# button.net
KiCad netlist of a schematic drawn in Altium Designer
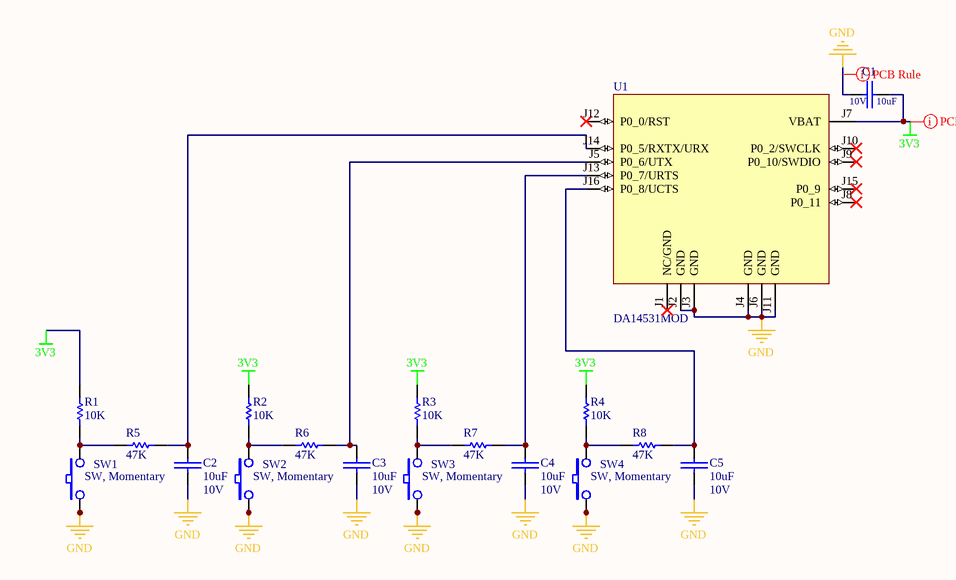
[diagram p0: button.SchDoc]

(export (version "E")
  (design (tool "Eeschema 10.0.6"))
  (components
    (comp (ref "C1")
      (value "10uF")
      (footprint "CAPC1608X10N")
      (description "Capacitor, 10uF, 10V, SM")
      (fields
        (field (name "MANUFACTURER'S PART #") "GRM188R61A106KE69D")
        (field (name "MANUFACTURER") "Murata")
        (field (name "VOLTAGE RATING") "10V")
      )
      (libsource (lib "Low Power Bluetooth PMOD RevA") (part "CI-10uF-10V-X5R-SR-MRT"))
    )
    (comp (ref "C2")
      (value "10uF")
      (footprint "CAPC1608X10N")
      (description "Capacitor, 10uF, 10V, SM")
      (fields
        (field (name "MANUFACTURER'S PART #") "GRM188R61A106KE69D")
        (field (name "MANUFACTURER") "Murata")
        (field (name "VOLTAGE RATING") "10V")
      )
      (libsource (lib "Low Power Bluetooth PMOD RevA") (part "CI-10uF-10V-X5R-SR-MRT"))
    )
    (comp (ref "C3")
      (value "10uF")
      (footprint "CAPC1608X10N")
      (description "Capacitor, 10uF, 10V, SM")
      (fields
        (field (name "MANUFACTURER'S PART #") "GRM188R61A106KE69D")
        (field (name "MANUFACTURER") "Murata")
        (field (name "VOLTAGE RATING") "10V")
      )
      (libsource (lib "Low Power Bluetooth PMOD RevA") (part "CI-10uF-10V-X5R-SR-MRT"))
    )
    (comp (ref "C4")
      (value "10uF")
      (footprint "CAPC1608X10N")
      (description "Capacitor, 10uF, 10V, SM")
      (fields
        (field (name "MANUFACTURER'S PART #") "GRM188R61A106KE69D")
        (field (name "MANUFACTURER") "Murata")
        (field (name "VOLTAGE RATING") "10V")
      )
      (libsource (lib "Low Power Bluetooth PMOD RevA") (part "CI-10uF-10V-X5R-SR-MRT"))
    )
    (comp (ref "C5")
      (value "10uF")
      (footprint "CAPC1608X10N")
      (description "Capacitor, 10uF, 10V, SM")
      (fields
        (field (name "MANUFACTURER'S PART #") "GRM188R61A106KE69D")
        (field (name "MANUFACTURER") "Murata")
        (field (name "VOLTAGE RATING") "10V")
      )
      (libsource (lib "Low Power Bluetooth PMOD RevA") (part "CI-10uF-10V-X5R-SR-MRT"))
    )
    (comp (ref "R1")
      (value "10K")
      (footprint "RESC1608X06N")
      (description "Resistor, 10K ohms, 1/8W, 1%, SM")
      (fields
        (field (name "MANUFACTURER'S PART #") "RK73H1JTTD1002F")
        (field (name "MANUFACTURER") "KOA Speer")
      )
      (libsource (lib "Low Power Bluetooth PMOD RevA") (part "RP-10K-SR-KOA"))
    )
    (comp (ref "R2")
      (value "10K")
      (footprint "RESC1608X06N")
      (description "Resistor, 10K ohms, 1/8W, 1%, SM")
      (fields
        (field (name "MANUFACTURER'S PART #") "RK73H1JTTD1002F")
        (field (name "MANUFACTURER") "KOA Speer")
      )
      (libsource (lib "Low Power Bluetooth PMOD RevA") (part "RP-10K-SR-KOA"))
    )
    (comp (ref "R3")
      (value "10K")
      (footprint "RESC1608X06N")
      (description "Resistor, 10K ohms, 1/8W, 1%, SM")
      (fields
        (field (name "MANUFACTURER'S PART #") "RK73H1JTTD1002F")
        (field (name "MANUFACTURER") "KOA Speer")
      )
      (libsource (lib "Low Power Bluetooth PMOD RevA") (part "RP-10K-SR-KOA"))
    )
    (comp (ref "R4")
      (value "10K")
      (footprint "RESC1608X06N")
      (description "Resistor, 10K ohms, 1/8W, 1%, SM")
      (fields
        (field (name "MANUFACTURER'S PART #") "RK73H1JTTD1002F")
        (field (name "MANUFACTURER") "KOA Speer")
      )
      (libsource (lib "Low Power Bluetooth PMOD RevA") (part "RP-10K-SR-KOA"))
    )
    (comp (ref "R5")
      (value "47K")
      (footprint "RESC1608X06N")
      (description "Resistor, 47K ohms, 1/8W, 1%, SM")
      (fields
        (field (name "MANUFACTURER'S PART #") "RK73H1JTTD6802F")
        (field (name "MANUFACTURER") "KOA Speer")
      )
      (libsource (lib "Low Power Bluetooth PMOD RevA") (part "RP-47K-SR-KOA"))
    )
    (comp (ref "R6")
      (value "47K")
      (footprint "RESC1608X06N")
      (description "Resistor, 47K ohms, 1/8W, 1%, SM")
      (fields
        (field (name "MANUFACTURER'S PART #") "RK73H1JTTD6802F")
        (field (name "MANUFACTURER") "KOA Speer")
      )
      (libsource (lib "Low Power Bluetooth PMOD RevA") (part "RP-47K-SR-KOA"))
    )
    (comp (ref "R7")
      (value "47K")
      (footprint "RESC1608X06N")
      (description "Resistor, 47K ohms, 1/8W, 1%, SM")
      (fields
        (field (name "MANUFACTURER'S PART #") "RK73H1JTTD6802F")
        (field (name "MANUFACTURER") "KOA Speer")
      )
      (libsource (lib "Low Power Bluetooth PMOD RevA") (part "RP-47K-SR-KOA"))
    )
    (comp (ref "R8")
      (value "47K")
      (footprint "RESC1608X06N")
      (description "Resistor, 47K ohms, 1/8W, 1%, SM")
      (fields
        (field (name "MANUFACTURER'S PART #") "RK73H1JTTD6802F")
        (field (name "MANUFACTURER") "KOA Speer")
      )
      (libsource (lib "Low Power Bluetooth PMOD RevA") (part "RP-47K-SR-KOA"))
    )
    (comp (ref "SW1")
      (value "SW, Momentary")
      (footprint "SW_PTS810")
      (description "Switch, Pushbutton, Top Actuated, SM")
      (fields
        (field (name "MANUFACTURER'S PART #") "PTS810 SJG 250 SMTR LFS")
        (field (name "MANUFACTURER") "C&K Components")
      )
      (libsource (lib "Low Power Bluetooth PMOD RevA") (part "SW-PTS810SJG250-SR-CKC"))
    )
    (comp (ref "SW2")
      (value "SW, Momentary")
      (footprint "SW_PTS810")
      (description "Switch, Pushbutton, Top Actuated, SM")
      (fields
        (field (name "MANUFACTURER'S PART #") "PTS810 SJG 250 SMTR LFS")
        (field (name "MANUFACTURER") "C&K Components")
      )
      (libsource (lib "Low Power Bluetooth PMOD RevA") (part "SW-PTS810SJG250-SR-CKC"))
    )
    (comp (ref "SW3")
      (value "SW, Momentary")
      (footprint "SW_PTS810")
      (description "Switch, Pushbutton, Top Actuated, SM")
      (fields
        (field (name "MANUFACTURER'S PART #") "PTS810 SJG 250 SMTR LFS")
        (field (name "MANUFACTURER") "C&K Components")
      )
      (libsource (lib "Low Power Bluetooth PMOD RevA") (part "SW-PTS810SJG250-SR-CKC"))
    )
    (comp (ref "SW4")
      (value "SW, Momentary")
      (footprint "SW_PTS810")
      (description "Switch, Pushbutton, Top Actuated, SM")
      (fields
        (field (name "MANUFACTURER'S PART #") "PTS810 SJG 250 SMTR LFS")
        (field (name "MANUFACTURER") "C&K Components")
      )
      (libsource (lib "Low Power Bluetooth PMOD RevA") (part "SW-PTS810SJG250-SR-CKC"))
    )
    (comp (ref "U1")
      (value "DA14531MOD")
      (footprint "DLG_DA14531MOD-00F01002")
      (description "DA14531MOD, Bluetooth Low Energy 5.1 Module, SM")
      (libsource (lib "Low Power Bluetooth PMOD RevA") (part "UD-DA14531MOD-00F01002-SR-DLG"))
    )
  )
  (nets
    (net (code "1") (name "3V3") (class "Default")
      (node (ref "C1") (pin "1") (pinfunction "1_1") (pintype "passive"))
      (node (ref "R1") (pin "1") (pinfunction "1_1") (pintype "passive"))
      (node (ref "R2") (pin "1") (pinfunction "1_1") (pintype "passive"))
      (node (ref "R3") (pin "1") (pinfunction "1_1") (pintype "passive"))
      (node (ref "R4") (pin "1") (pinfunction "1_1") (pintype "passive"))
      (node (ref "U1") (pin "J7") (pinfunction "VBAT_J7") (pintype "power_in"))
    )
    (net (code "2") (name "GND") (class "Default")
      (node (ref "C1") (pin "2") (pinfunction "2_2") (pintype "passive"))
      (node (ref "C2") (pin "2") (pinfunction "2_2") (pintype "passive"))
      (node (ref "C3") (pin "2") (pinfunction "2_2") (pintype "passive"))
      (node (ref "C4") (pin "2") (pinfunction "2_2") (pintype "passive"))
      (node (ref "C5") (pin "2") (pinfunction "2_2") (pintype "passive"))
      (node (ref "SW1") (pin "1") (pinfunction "1_1") (pintype "passive"))
      (node (ref "SW1") (pin "2") (pinfunction "2_2") (pintype "passive"))
      (node (ref "SW2") (pin "1") (pinfunction "1_1") (pintype "passive"))
      (node (ref "SW2") (pin "2") (pinfunction "2_2") (pintype "passive"))
      (node (ref "SW3") (pin "1") (pinfunction "1_1") (pintype "passive"))
      (node (ref "SW3") (pin "2") (pinfunction "2_2") (pintype "passive"))
      (node (ref "SW4") (pin "1") (pinfunction "1_1") (pintype "passive"))
      (node (ref "SW4") (pin "2") (pinfunction "2_2") (pintype "passive"))
      (node (ref "U1") (pin "J11") (pinfunction "GND_J11") (pintype "power_in"))
      (node (ref "U1") (pin "J2") (pinfunction "GND_J2") (pintype "power_in"))
      (node (ref "U1") (pin "J3") (pinfunction "GND_J3") (pintype "power_in"))
      (node (ref "U1") (pin "J4") (pinfunction "GND_J4") (pintype "power_in"))
      (node (ref "U1") (pin "J6") (pinfunction "GND_J6") (pintype "power_in"))
    )
    (net (code "3") (name "Net-(R1-Pad2)") (class "Default")
      (node (ref "R1") (pin "2") (pinfunction "2_2") (pintype "passive"))
      (node (ref "R5") (pin "1") (pinfunction "1_1") (pintype "passive"))
      (node (ref "SW1") (pin "3") (pinfunction "3_3") (pintype "passive"))
      (node (ref "SW1") (pin "4") (pinfunction "4_4") (pintype "passive"))
    )
    (net (code "4") (name "Net-(R2-Pad2)") (class "Default")
      (node (ref "R2") (pin "2") (pinfunction "2_2") (pintype "passive"))
      (node (ref "R6") (pin "1") (pinfunction "1_1") (pintype "passive"))
      (node (ref "SW2") (pin "3") (pinfunction "3_3") (pintype "passive"))
      (node (ref "SW2") (pin "4") (pinfunction "4_4") (pintype "passive"))
    )
    (net (code "5") (name "Net-(R3-Pad2)") (class "Default")
      (node (ref "R3") (pin "2") (pinfunction "2_2") (pintype "passive"))
      (node (ref "R7") (pin "1") (pinfunction "1_1") (pintype "passive"))
      (node (ref "SW3") (pin "3") (pinfunction "3_3") (pintype "passive"))
      (node (ref "SW3") (pin "4") (pinfunction "4_4") (pintype "passive"))
    )
    (net (code "6") (name "Net-(R4-Pad2)") (class "Default")
      (node (ref "R4") (pin "2") (pinfunction "2_2") (pintype "passive"))
      (node (ref "R8") (pin "1") (pinfunction "1_1") (pintype "passive"))
      (node (ref "SW4") (pin "3") (pinfunction "3_3") (pintype "passive"))
      (node (ref "SW4") (pin "4") (pinfunction "4_4") (pintype "passive"))
    )
    (net (code "7") (name "Net-(U1-P0_5{slash}RXTX{slash}URX)") (class "Default")
      (node (ref "C2") (pin "1") (pinfunction "1_1") (pintype "passive"))
      (node (ref "R5") (pin "2") (pinfunction "2_2") (pintype "passive"))
      (node (ref "U1") (pin "J14") (pinfunction "P0_5/RXTX/URX_J14") (pintype "bidirectional"))
    )
    (net (code "8") (name "Net-(U1-P0_6{slash}UTX)") (class "Default")
      (node (ref "C3") (pin "1") (pinfunction "1_1") (pintype "passive"))
      (node (ref "R6") (pin "2") (pinfunction "2_2") (pintype "passive"))
      (node (ref "U1") (pin "J5") (pinfunction "P0_6/UTX_J5") (pintype "bidirectional"))
    )
    (net (code "9") (name "Net-(U1-P0_7{slash}URTS)") (class "Default")
      (node (ref "C4") (pin "1") (pinfunction "1_1") (pintype "passive"))
      (node (ref "R7") (pin "2") (pinfunction "2_2") (pintype "passive"))
      (node (ref "U1") (pin "J13") (pinfunction "P0_7/URTS_J13") (pintype "bidirectional"))
    )
    (net (code "10") (name "Net-(U1-P0_8{slash}UCTS)") (class "Default")
      (node (ref "C5") (pin "1") (pinfunction "1_1") (pintype "passive"))
      (node (ref "R8") (pin "2") (pinfunction "2_2") (pintype "passive"))
      (node (ref "U1") (pin "J16") (pinfunction "P0_8/UCTS_J16") (pintype "bidirectional"))
    )
    (net (code "11") (name "unconnected-(U1-NC{slash}GND-PadJ1)") (class "Default")
      (node (ref "U1") (pin "J1") (pinfunction "NC/GND_J1") (pintype "power_in+no_connect"))
    )
    (net (code "12") (name "unconnected-(U1-P0_0{slash}RST-PadJ12)") (class "Default")
      (node (ref "U1") (pin "J12") (pinfunction "P0_0/RST_J12") (pintype "bidirectional+no_connect"))
    )
    (net (code "13") (name "unconnected-(U1-P0_2{slash}SWCLK-PadJ10)") (class "Default")
      (node (ref "U1") (pin "J10") (pinfunction "P0_2/SWCLK_J10") (pintype "bidirectional+no_connect"))
    )
    (net (code "14") (name "unconnected-(U1-P0_9-PadJ15)") (class "Default")
      (node (ref "U1") (pin "J15") (pinfunction "P0_9_J15") (pintype "bidirectional+no_connect"))
    )
    (net (code "15") (name "unconnected-(U1-P0_10{slash}SWDIO-PadJ9)") (class "Default")
      (node (ref "U1") (pin "J9") (pinfunction "P0_10/SWDIO_J9") (pintype "bidirectional+no_connect"))
    )
    (net (code "16") (name "unconnected-(U1-P0_11-PadJ8)") (class "Default")
      (node (ref "U1") (pin "J8") (pinfunction "P0_11_J8") (pintype "bidirectional+no_connect"))
    )
  )
)
